# MR_EMG_Force_Shield.net
KiCad netlist of a schematic drawn in EAGLE
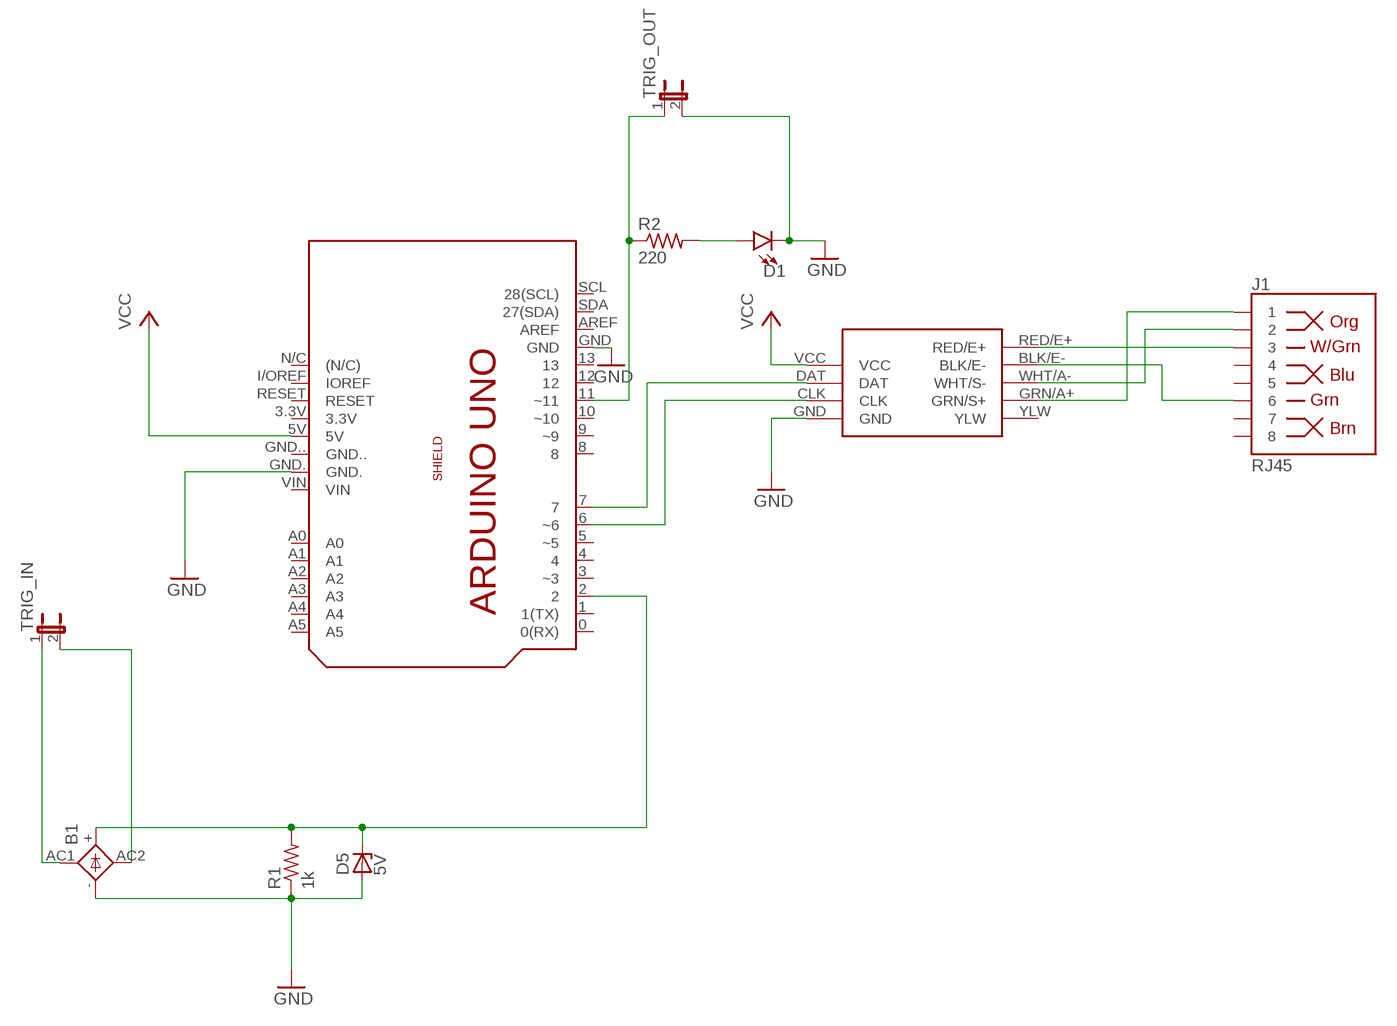
[diagram p0: schematic, sheet 1]

(export (version "E")
  (design (tool "Eeschema 10.0.6"))
  (components
    (comp (ref "B1")
      (value "1KAB")
      (footprint "eagle-import:1KAB")
      (libsource (lib "eagle-import") (part "1KAB"))
    )
    (comp (ref "D1")
      (value "LED5MM")
      (footprint "eagle-import:LED_5MM")
      (libsource (lib "eagle-import") (part "LED5MM"))
    )
    (comp (ref "D5")
      (value "5V")
      (footprint "eagle-import:DO41Z10")
      (libsource (lib "eagle-import") (part "ZENER-DIODEDO41Z10"))
    )
    (comp (ref "J1")
      (value "RJ45")
      (footprint "eagle-import:RJ45-8")
      (libsource (lib "eagle-import") (part "RJ45-8"))
    )
    (comp (ref "PCB1")
      (value "ARDUINO_UNO_SHIELDNOPCB")
      (footprint "eagle-import:ARDUINO_UNO_SHIELD_NOPCB")
      (libsource (lib "eagle-import") (part "ARDUINO_UNO_SHIELDNOPCB"))
    )
    (comp (ref "R1")
      (value "1k")
      (footprint "eagle-import:0204_7")
      (libsource (lib "eagle-import") (part "R-US_0204/7"))
    )
    (comp (ref "R2")
      (value "220")
      (footprint "eagle-import:0204_7")
      (libsource (lib "eagle-import") (part "R-US_0204/7"))
    )
    (comp (ref "TRIG_IN")
      (value "JUMPER-2PTH")
      (footprint "eagle-import:1X02")
      (libsource (lib "eagle-import") (part "JUMPER-2PTH"))
    )
    (comp (ref "TRIG_OUT")
      (value "JUMPER-2PTH")
      (footprint "eagle-import:1X02")
      (libsource (lib "eagle-import") (part "JUMPER-2PTH"))
    )
    (comp (ref "U$2")
      (value "EBAY_HX711_PURPLE")
      (footprint "eagle-import:EBAY_HX711_PURPLE_BRD")
      (libsource (lib "eagle-import") (part "EBAY_HX711_PURPLE"))
    )
  )
  (nets
    (net (code "1") (name "GND") (class "Default")
      (node (ref "B1") (pin "-") (pinfunction "-_-") (pintype "passive"))
      (node (ref "D1") (pin "K") (pinfunction "C_K") (pintype "passive"))
      (node (ref "D5") (pin "A") (pinfunction "A_A") (pintype "passive"))
      (node (ref "PCB1") (pin "GND") (pinfunction "GND_GND") (pintype "bidirectional"))
      (node (ref "PCB1") (pin "GND.") (pinfunction "GND._GND.") (pintype "bidirectional"))
      (node (ref "R1") (pin "1") (pinfunction "1_1") (pintype "passive"))
      (node (ref "TRIG_OUT") (pin "2") (pinfunction "2_2") (pintype "passive"))
      (node (ref "U$2") (pin "GND") (pinfunction "GND_GND") (pintype "bidirectional"))
    )
    (net (code "2") (name "Net-(B1-Pad+)") (class "Default")
      (node (ref "B1") (pin "+") (pinfunction "+_+") (pintype "passive"))
      (node (ref "D5") (pin "C") (pinfunction "C_C") (pintype "passive"))
      (node (ref "PCB1") (pin "2") (pinfunction "2_2") (pintype "bidirectional"))
      (node (ref "R1") (pin "2") (pinfunction "2_2") (pintype "passive"))
    )
    (net (code "3") (name "Net-(B1-PadAC1)") (class "Default")
      (node (ref "B1") (pin "AC1") (pinfunction "AC1_AC1") (pintype "passive"))
      (node (ref "TRIG_IN") (pin "1") (pinfunction "1_1") (pintype "passive"))
    )
    (net (code "4") (name "Net-(B1-PadAC2)") (class "Default")
      (node (ref "B1") (pin "AC2") (pinfunction "AC2_AC2") (pintype "passive"))
      (node (ref "TRIG_IN") (pin "2") (pinfunction "2_2") (pintype "passive"))
    )
    (net (code "5") (name "Net-(D1-PadA)") (class "Default")
      (node (ref "D1") (pin "A") (pinfunction "A_A") (pintype "passive"))
      (node (ref "R2") (pin "2") (pinfunction "2_2") (pintype "passive"))
    )
    (net (code "6") (name "Net-(J1-Pad3)") (class "Default")
      (node (ref "J1") (pin "3") (pinfunction "3_3") (pintype "bidirectional"))
      (node (ref "U$2") (pin "RED/E+") (pinfunction "RED/E+_RED/E+") (pintype "bidirectional"))
    )
    (net (code "7") (name "Net-(J1-Pad6)") (class "Default")
      (node (ref "J1") (pin "6") (pinfunction "6_6") (pintype "bidirectional"))
      (node (ref "U$2") (pin "BLK/E-") (pinfunction "BLK/E-_BLK/E-") (pintype "bidirectional"))
    )
    (net (code "8") (name "Net-(PCB1-Pad7)") (class "Default")
      (node (ref "PCB1") (pin "7") (pinfunction "7_7") (pintype "bidirectional"))
      (node (ref "U$2") (pin "DAT") (pinfunction "DAT_DAT") (pintype "bidirectional"))
    )
    (net (code "9") (name "Net-(PCB1-~{6})") (class "Default")
      (node (ref "PCB1") (pin "6") (pinfunction "~{6}_6") (pintype "bidirectional"))
      (node (ref "U$2") (pin "CLK") (pinfunction "CLK_CLK") (pintype "bidirectional"))
    )
    (net (code "10") (name "Net-(PCB1-~{11})") (class "Default")
      (node (ref "PCB1") (pin "11") (pinfunction "~{11}_11") (pintype "bidirectional"))
      (node (ref "R2") (pin "1") (pinfunction "1_1") (pintype "passive"))
      (node (ref "TRIG_OUT") (pin "1") (pinfunction "1_1") (pintype "passive"))
    )
    (net (code "11") (name "Net-(U$2-GRN{slash}S+)") (class "Default")
      (node (ref "J1") (pin "1") (pinfunction "1_1") (pintype "bidirectional"))
      (node (ref "U$2") (pin "GRN/A+") (pinfunction "GRN/S+_GRN/A+") (pintype "bidirectional"))
    )
    (net (code "12") (name "Net-(U$2-WHT{slash}S-)") (class "Default")
      (node (ref "J1") (pin "2") (pinfunction "2_2") (pintype "bidirectional"))
      (node (ref "U$2") (pin "WHT/A-") (pinfunction "WHT/S-_WHT/A-") (pintype "bidirectional"))
    )
    (net (code "13") (name "VCC") (class "Default")
      (node (ref "PCB1") (pin "5V") (pinfunction "5V_5V") (pintype "bidirectional"))
      (node (ref "U$2") (pin "VCC") (pinfunction "VCC_VCC") (pintype "bidirectional"))
    )
    (net (code "14") (name "unconnected-(J1-Pad4)") (class "Default")
      (node (ref "J1") (pin "4") (pinfunction "4_4") (pintype "bidirectional"))
    )
    (net (code "15") (name "unconnected-(J1-Pad5)") (class "Default")
      (node (ref "J1") (pin "5") (pinfunction "5_5") (pintype "bidirectional"))
    )
    (net (code "16") (name "unconnected-(J1-Pad7)") (class "Default")
      (node (ref "J1") (pin "7") (pinfunction "7_7") (pintype "bidirectional"))
    )
    (net (code "17") (name "unconnected-(J1-Pad8)") (class "Default")
      (node (ref "J1") (pin "8") (pinfunction "8_8") (pintype "bidirectional"))
    )
    (net (code "18") (name "unconnected-(PCB1-(N{slash}C)-PadN{slash}C)") (class "Default")
      (node (ref "PCB1") (pin "N/C") (pinfunction "(N/C)_N/C") (pintype "bidirectional"))
    )
    (net (code "19") (name "unconnected-(PCB1-0(RX)-Pad0)") (class "Default")
      (node (ref "PCB1") (pin "0") (pinfunction "0(RX)_0") (pintype "bidirectional"))
    )
    (net (code "20") (name "unconnected-(PCB1-1(TX)-Pad1)") (class "Default")
      (node (ref "PCB1") (pin "1") (pinfunction "1(TX)_1") (pintype "bidirectional"))
    )
    (net (code "21") (name "unconnected-(PCB1-27(SDA)-PadSDA)") (class "Default")
      (node (ref "PCB1") (pin "SDA") (pinfunction "27(SDA)_SDA") (pintype "bidirectional"))
    )
    (net (code "22") (name "unconnected-(PCB1-28(SCL)-PadSCL)") (class "Default")
      (node (ref "PCB1") (pin "SCL") (pinfunction "28(SCL)_SCL") (pintype "bidirectional"))
    )
    (net (code "23") (name "unconnected-(PCB1-IOREF-PadI{slash}OREF)") (class "Default")
      (node (ref "PCB1") (pin "I/OREF") (pinfunction "IOREF_I/OREF") (pintype "bidirectional"))
    )
    (net (code "24") (name "unconnected-(PCB1-Pad3.3V)") (class "Default")
      (node (ref "PCB1") (pin "3.3V") (pinfunction "3.3V_3.3V") (pintype "bidirectional"))
    )
    (net (code "25") (name "unconnected-(PCB1-Pad4)") (class "Default")
      (node (ref "PCB1") (pin "4") (pinfunction "4_4") (pintype "bidirectional"))
    )
    (net (code "26") (name "unconnected-(PCB1-Pad8)") (class "Default")
      (node (ref "PCB1") (pin "8") (pinfunction "8_8") (pintype "bidirectional"))
    )
    (net (code "27") (name "unconnected-(PCB1-Pad12)") (class "Default")
      (node (ref "PCB1") (pin "12") (pinfunction "12_12") (pintype "bidirectional"))
    )
    (net (code "28") (name "unconnected-(PCB1-Pad13)") (class "Default")
      (node (ref "PCB1") (pin "13") (pinfunction "13_13") (pintype "bidirectional"))
    )
    (net (code "29") (name "unconnected-(PCB1-PadA0)") (class "Default")
      (node (ref "PCB1") (pin "A0") (pinfunction "A0_A0") (pintype "bidirectional"))
    )
    (net (code "30") (name "unconnected-(PCB1-PadA1)") (class "Default")
      (node (ref "PCB1") (pin "A1") (pinfunction "A1_A1") (pintype "bidirectional"))
    )
    (net (code "31") (name "unconnected-(PCB1-PadA2)") (class "Default")
      (node (ref "PCB1") (pin "A2") (pinfunction "A2_A2") (pintype "bidirectional"))
    )
    (net (code "32") (name "unconnected-(PCB1-PadA3)") (class "Default")
      (node (ref "PCB1") (pin "A3") (pinfunction "A3_A3") (pintype "bidirectional"))
    )
    (net (code "33") (name "unconnected-(PCB1-PadA4)") (class "Default")
      (node (ref "PCB1") (pin "A4") (pinfunction "A4_A4") (pintype "bidirectional"))
    )
    (net (code "34") (name "unconnected-(PCB1-PadA5)") (class "Default")
      (node (ref "PCB1") (pin "A5") (pinfunction "A5_A5") (pintype "bidirectional"))
    )
    (net (code "35") (name "unconnected-(PCB1-PadAREF)") (class "Default")
      (node (ref "PCB1") (pin "AREF") (pinfunction "AREF_AREF") (pintype "bidirectional"))
    )
    (net (code "36") (name "unconnected-(PCB1-PadGND..)") (class "Default")
      (node (ref "PCB1") (pin "GND..") (pinfunction "GND.._GND..") (pintype "bidirectional"))
    )
    (net (code "37") (name "unconnected-(PCB1-PadRESET)") (class "Default")
      (node (ref "PCB1") (pin "RESET") (pinfunction "RESET_RESET") (pintype "bidirectional"))
    )
    (net (code "38") (name "unconnected-(PCB1-PadVIN)") (class "Default")
      (node (ref "PCB1") (pin "VIN") (pinfunction "VIN_VIN") (pintype "bidirectional"))
    )
    (net (code "39") (name "unconnected-(PCB1-~{3}-Pad3)") (class "Default")
      (node (ref "PCB1") (pin "3") (pinfunction "~{3}_3") (pintype "bidirectional"))
    )
    (net (code "40") (name "unconnected-(PCB1-~{5}-Pad5)") (class "Default")
      (node (ref "PCB1") (pin "5") (pinfunction "~{5}_5") (pintype "bidirectional"))
    )
    (net (code "41") (name "unconnected-(PCB1-~{9}-Pad9)") (class "Default")
      (node (ref "PCB1") (pin "9") (pinfunction "~{9}_9") (pintype "bidirectional"))
    )
    (net (code "42") (name "unconnected-(PCB1-~{10}-Pad10)") (class "Default")
      (node (ref "PCB1") (pin "10") (pinfunction "~{10}_10") (pintype "bidirectional"))
    )
    (net (code "43") (name "unconnected-(U$2-PadYLW)") (class "Default")
      (node (ref "U$2") (pin "YLW") (pinfunction "YLW_YLW") (pintype "bidirectional"))
    )
  )
)
